# slo.net
KiCad netlist of a schematic drawn in EAGLE
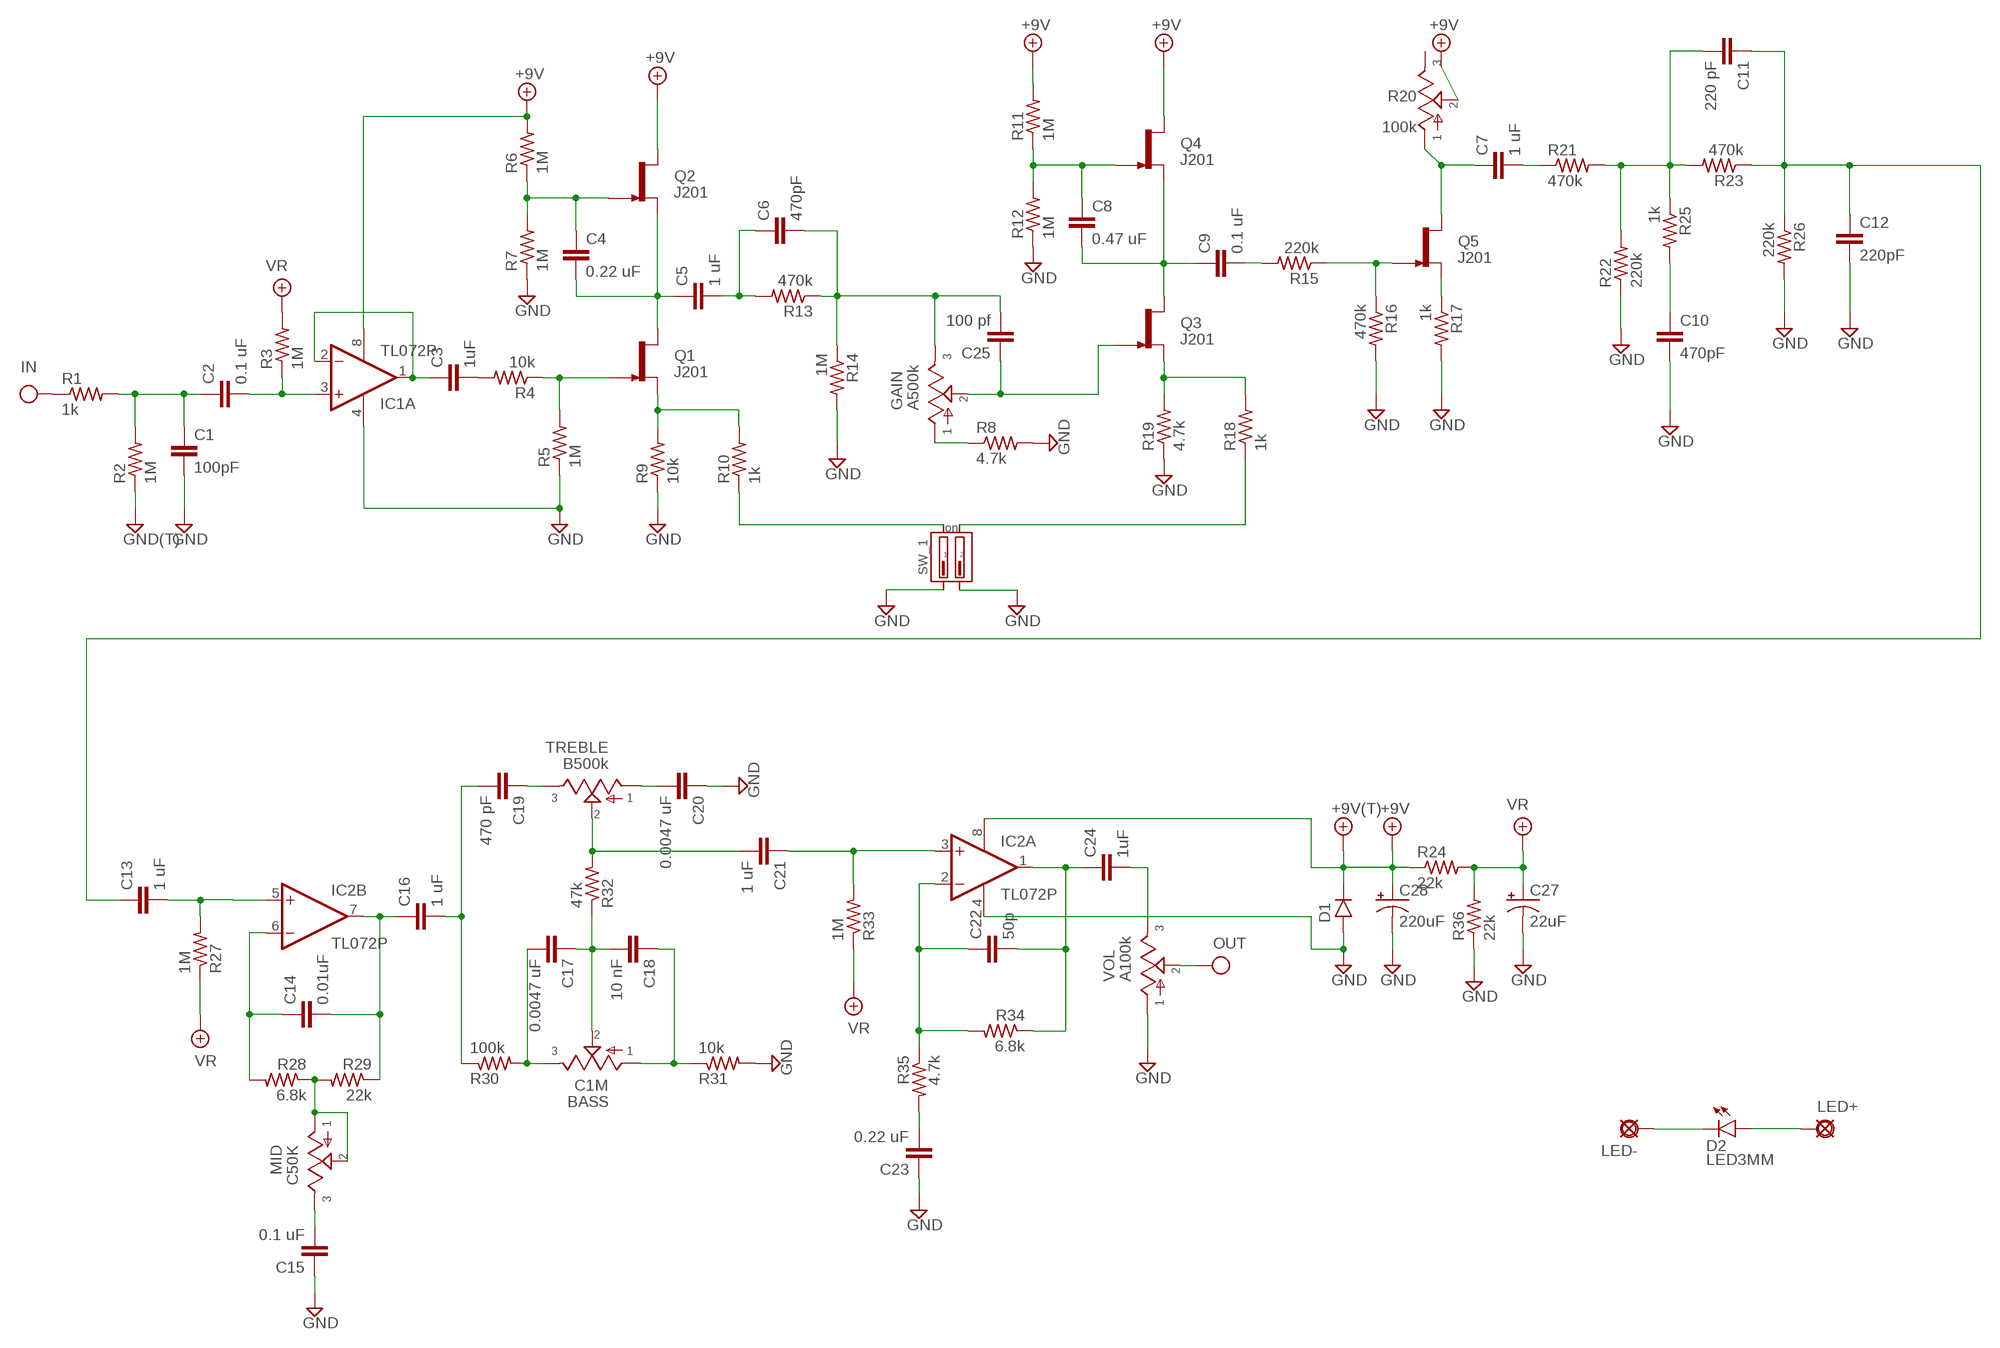
[diagram p0: schematic, sheet 1]

(export (version "E")
  (design (tool "Eeschema 10.0.6"))
  (components
    (comp (ref "+9V")
      (value "+9V(T)")
      (footprint "eagle-import:SQUARE")
      (libsource (lib "eagle-import") (part "+9V(T)"))
    )
    (comp (ref "BASS")
      (value "C1M")
      (footprint "eagle-import:16MM")
      (libsource (lib "eagle-import") (part "POT16MM"))
    )
    (comp (ref "C1")
      (value "100pF")
      (footprint "eagle-import:050X030_050")
      (libsource (lib "eagle-import") (part "050X030_0502"))
    )
    (comp (ref "C2")
      (value "0.1 uF")
      (footprint "eagle-import:080X045")
      (libsource (lib "eagle-import") (part "080X0452"))
    )
    (comp (ref "C3")
      (value "1uF")
      (footprint "eagle-import:080X050")
      (libsource (lib "eagle-import") (part "080X0502"))
    )
    (comp (ref "C4")
      (value "0.22 uF")
      (footprint "eagle-import:080X045")
      (libsource (lib "eagle-import") (part "080X0452"))
    )
    (comp (ref "C5")
      (value "1 uF")
      (footprint "eagle-import:070X030")
      (libsource (lib "eagle-import") (part "070X0302"))
    )
    (comp (ref "C6")
      (value "470pF")
      (footprint "eagle-import:050X030_050")
      (libsource (lib "eagle-import") (part "050X030_0502"))
    )
    (comp (ref "C7")
      (value "1 uF")
      (footprint "eagle-import:080X050")
      (libsource (lib "eagle-import") (part "080X0502"))
    )
    (comp (ref "C8")
      (value "0.47 uF")
      (footprint "eagle-import:080X045")
      (libsource (lib "eagle-import") (part "080X0452"))
    )
    (comp (ref "C9")
      (value "0.1 uF")
      (footprint "eagle-import:080X045")
      (libsource (lib "eagle-import") (part "080X0452"))
    )
    (comp (ref "C10")
      (value "470pF")
      (footprint "eagle-import:070X030")
      (libsource (lib "eagle-import") (part "070X0302"))
    )
    (comp (ref "C11")
      (value "220 pF")
      (footprint "eagle-import:075X035_3")
      (libsource (lib "eagle-import") (part "075X0353"))
    )
    (comp (ref "C12")
      (value "220pF")
      (footprint "eagle-import:075X035_3")
      (libsource (lib "eagle-import") (part "075X0353"))
    )
    (comp (ref "C13")
      (value "1 uF")
      (footprint "eagle-import:080X050")
      (libsource (lib "eagle-import") (part "080X0502"))
    )
    (comp (ref "C14")
      (value "0.01uF")
      (footprint "eagle-import:050X030_050_1")
      (libsource (lib "eagle-import") (part "050X030_0501"))
    )
    (comp (ref "C15")
      (value "0.1 uF")
      (footprint "eagle-import:075X040_3")
      (libsource (lib "eagle-import") (part "080X0453"))
    )
    (comp (ref "C16")
      (value "1 uF")
      (footprint "eagle-import:080X050")
      (libsource (lib "eagle-import") (part "080X0502"))
    )
    (comp (ref "C17")
      (value "0.0047 uF")
      (footprint "eagle-import:075X035")
      (libsource (lib "eagle-import") (part "075X0352"))
    )
    (comp (ref "C18")
      (value "10 nF")
      (footprint "eagle-import:075X035")
      (libsource (lib "eagle-import") (part "075X0352"))
    )
    (comp (ref "C19")
      (value "470 pF")
      (footprint "eagle-import:075X030")
      (libsource (lib "eagle-import") (part "075X0302"))
    )
    (comp (ref "C20")
      (value "0.0047 uF")
      (footprint "eagle-import:075X035")
      (libsource (lib "eagle-import") (part "075X0352"))
    )
    (comp (ref "C21")
      (value "1 uF")
      (footprint "eagle-import:080X050")
      (libsource (lib "eagle-import") (part "080X0502"))
    )
    (comp (ref "C22")
      (value "50p")
      (footprint "eagle-import:050X030_050_1")
      (libsource (lib "eagle-import") (part "050X030_0501"))
    )
    (comp (ref "C23")
      (value "0.22 uF")
      (footprint "eagle-import:080X045")
      (libsource (lib "eagle-import") (part "080X0452"))
    )
    (comp (ref "C24")
      (value "1uF")
      (footprint "eagle-import:080X050")
      (libsource (lib "eagle-import") (part "080X0502"))
    )
    (comp (ref "C25")
      (value "100 pf")
      (footprint "eagle-import:050X030_050_1")
      (libsource (lib "eagle-import") (part "050X030_0501"))
    )
    (comp (ref "C27")
      (value "22uF")
      (footprint "eagle-import:050_020")
      (libsource (lib "eagle-import") (part "050"))
    )
    (comp (ref "C28")
      (value "220uF")
      (footprint "eagle-import:063_025")
      (libsource (lib "eagle-import") (part "0631"))
    )
    (comp (ref "D1")
      (value "1N400X.1")
      (footprint "eagle-import:DO41-1")
      (libsource (lib "eagle-import") (part "1N400X.1"))
    )
    (comp (ref "D2")
      (value "LED3MM")
      (footprint "eagle-import:LED3MM")
      (libsource (lib "eagle-import") (part "LED3MM"))
    )
    (comp (ref "GAIN")
      (value "A500k")
      (footprint "eagle-import:16MM")
      (libsource (lib "eagle-import") (part "POT16MM"))
    )
    (comp (ref "GND")
      (value "GND(T)")
      (footprint "eagle-import:SQUARE")
      (libsource (lib "eagle-import") (part "GND(T)"))
    )
    (comp (ref "IC1")
      (value "TL072P")
      (footprint "eagle-import:DIL08")
      (libsource (lib "eagle-import") (part "TL072P"))
    )
    (comp (ref "IC2")
      (value "TL072P")
      (footprint "eagle-import:DIL08")
      (libsource (lib "eagle-import") (part "TL072P"))
    )
    (comp (ref "IN")
      (value "IN(T)")
      (footprint "eagle-import:SQUARE")
      (fields (field (name "SPICEPREFIX") "I"))
      (libsource (lib "eagle-import") (part "IN(T)"))
    )
    (comp (ref "LED+")
      (value "PADO")
      (footprint "eagle-import:ROUND")
      (libsource (lib "eagle-import") (part "PADO"))
    )
    (comp (ref "LED-")
      (value "PAD")
      (footprint "eagle-import:SQUARE")
      (libsource (lib "eagle-import") (part "PAD"))
    )
    (comp (ref "MID")
      (value "C50K")
      (footprint "eagle-import:16MM")
      (libsource (lib "eagle-import") (part "POT16MM"))
    )
    (comp (ref "OUT")
      (value "OUT(T)")
      (footprint "eagle-import:SQUARE")
      (libsource (lib "eagle-import") (part "OUT(T)"))
    )
    (comp (ref "Q1")
      (value "J201")
      (footprint "eagle-import:TO92-")
      (libsource (lib "eagle-import") (part "J201"))
    )
    (comp (ref "Q2")
      (value "J201")
      (footprint "eagle-import:TO92-")
      (libsource (lib "eagle-import") (part "J201"))
    )
    (comp (ref "Q3")
      (value "J201")
      (footprint "eagle-import:TO92-")
      (libsource (lib "eagle-import") (part "J201"))
    )
    (comp (ref "Q4")
      (value "J201")
      (footprint "eagle-import:TO92-")
      (libsource (lib "eagle-import") (part "J201"))
    )
    (comp (ref "Q5")
      (value "J201")
      (footprint "eagle-import:TO92-")
      (libsource (lib "eagle-import") (part "J201"))
    )
    (comp (ref "R1")
      (value "1k")
      (footprint "eagle-import:R0204_2")
      (libsource (lib "eagle-import") (part "3MM.2"))
    )
    (comp (ref "R2")
      (value "1M")
      (footprint "eagle-import:R0204_2")
      (libsource (lib "eagle-import") (part "3MM.2"))
    )
    (comp (ref "R3")
      (value "1M")
      (footprint "eagle-import:R0204_2")
      (libsource (lib "eagle-import") (part "3MM.2"))
    )
    (comp (ref "R4")
      (value "10k")
      (footprint "eagle-import:R0204_2")
      (libsource (lib "eagle-import") (part "3MM.2"))
    )
    (comp (ref "R5")
      (value "1M")
      (footprint "eagle-import:R0204_2")
      (libsource (lib "eagle-import") (part "3MM.2"))
    )
    (comp (ref "R6")
      (value "1M")
      (footprint "eagle-import:R0204_2")
      (libsource (lib "eagle-import") (part "3MM.2"))
    )
    (comp (ref "R7")
      (value "1M")
      (footprint "eagle-import:R0204_2")
      (libsource (lib "eagle-import") (part "3MM.2"))
    )
    (comp (ref "R8")
      (value "4.7k")
      (footprint "eagle-import:R0204_2")
      (libsource (lib "eagle-import") (part "3MM.2"))
    )
    (comp (ref "R9")
      (value "10k")
      (footprint "eagle-import:R0204_2")
      (libsource (lib "eagle-import") (part "3MM.2"))
    )
    (comp (ref "R10")
      (value "1k")
      (footprint "eagle-import:R0204_2")
      (libsource (lib "eagle-import") (part "3MM.2"))
    )
    (comp (ref "R11")
      (value "1M")
      (footprint "eagle-import:R0204_2")
      (libsource (lib "eagle-import") (part "3MM.2"))
    )
    (comp (ref "R12")
      (value "1M")
      (footprint "eagle-import:R0204_2")
      (libsource (lib "eagle-import") (part "3MM.2"))
    )
    (comp (ref "R13")
      (value "470k")
      (footprint "eagle-import:R0204_2")
      (libsource (lib "eagle-import") (part "3MM.2"))
    )
    (comp (ref "R14")
      (value "1M")
      (footprint "eagle-import:R0204_2")
      (libsource (lib "eagle-import") (part "3MM.2"))
    )
    (comp (ref "R15")
      (value "220k")
      (footprint "eagle-import:R0204_2")
      (libsource (lib "eagle-import") (part "3MM.2"))
    )
    (comp (ref "R16")
      (value "470k")
      (footprint "eagle-import:R0204_2")
      (libsource (lib "eagle-import") (part "3MM.2"))
    )
    (comp (ref "R17")
      (value "1k")
      (footprint "eagle-import:R0204_2")
      (libsource (lib "eagle-import") (part "3MM.2"))
    )
    (comp (ref "R18")
      (value "1k")
      (footprint "eagle-import:R0204_2")
      (libsource (lib "eagle-import") (part "3MM.2"))
    )
    (comp (ref "R19")
      (value "4.7k")
      (footprint "eagle-import:R0204_2")
      (libsource (lib "eagle-import") (part "3MM.2"))
    )
    (comp (ref "R20")
      (value "100k")
      (footprint "eagle-import:B25P")
      (libsource (lib "eagle-import") (part "POTTRIM"))
    )
    (comp (ref "R21")
      (value "470k")
      (footprint "eagle-import:R0204_2")
      (libsource (lib "eagle-import") (part "3MM.2"))
    )
    (comp (ref "R22")
      (value "220k")
      (footprint "eagle-import:R0204_2")
      (libsource (lib "eagle-import") (part "3MM.2"))
    )
    (comp (ref "R23")
      (value "470k")
      (footprint "eagle-import:R0204_2")
      (libsource (lib "eagle-import") (part "3MM.2"))
    )
    (comp (ref "R24")
      (value "22k")
      (footprint "eagle-import:R0204_2")
      (libsource (lib "eagle-import") (part "3MM.2"))
    )
    (comp (ref "R25")
      (value "1k")
      (footprint "eagle-import:R0204_2")
      (libsource (lib "eagle-import") (part "3MM.2"))
    )
    (comp (ref "R26")
      (value "220k")
      (footprint "eagle-import:R0204_2")
      (libsource (lib "eagle-import") (part "3MM.2"))
    )
    (comp (ref "R27")
      (value "1M")
      (footprint "eagle-import:R0204_2")
      (libsource (lib "eagle-import") (part "3MM.2"))
    )
    (comp (ref "R28")
      (value "6.8k")
      (footprint "eagle-import:R0204_2")
      (libsource (lib "eagle-import") (part "3MM.2"))
    )
    (comp (ref "R29")
      (value "22k")
      (footprint "eagle-import:R0204_2")
      (libsource (lib "eagle-import") (part "3MM.2"))
    )
    (comp (ref "R30")
      (value "100k")
      (footprint "eagle-import:R0204_2")
      (libsource (lib "eagle-import") (part "3MM.2"))
    )
    (comp (ref "R31")
      (value "10k")
      (footprint "eagle-import:R0204_2")
      (libsource (lib "eagle-import") (part "3MM.2"))
    )
    (comp (ref "R32")
      (value "47k")
      (footprint "eagle-import:R0204_2")
      (libsource (lib "eagle-import") (part "3MM.2"))
    )
    (comp (ref "R33")
      (value "1M")
      (footprint "eagle-import:R0204_2")
      (libsource (lib "eagle-import") (part "3MM.2"))
    )
    (comp (ref "R34")
      (value "6.8k")
      (footprint "eagle-import:R0204_2")
      (libsource (lib "eagle-import") (part "3MM.2"))
    )
    (comp (ref "R35")
      (value "4.7k")
      (footprint "eagle-import:R0204_2")
      (libsource (lib "eagle-import") (part "3MM.2"))
    )
    (comp (ref "R36")
      (value "22k")
      (footprint "eagle-import:R0204_2")
      (libsource (lib "eagle-import") (part "3MM.2"))
    )
    (comp (ref "SW_1")
      (value "DIP2")
      (footprint "eagle-import:DIP2.B")
      (libsource (lib "eagle-import") (part "DIP2"))
    )
    (comp (ref "TREBLE")
      (value "B500k")
      (footprint "eagle-import:16MM")
      (libsource (lib "eagle-import") (part "POT16MM"))
    )
    (comp (ref "VOL")
      (value "A100k")
      (footprint "eagle-import:16MM")
      (libsource (lib "eagle-import") (part "POT16MM"))
    )
  )
  (nets
    (net (code "1") (name "+9V") (class "Default")
      (node (ref "+9V") (pin "1") (pinfunction "+9V_1") (pintype "power_in"))
      (node (ref "C28") (pin "+") (pinfunction "+_+") (pintype "passive"))
      (node (ref "D1") (pin "C") (pinfunction "C_C") (pintype "passive"))
      (node (ref "IC1") (pin "8") (pinfunction "V+_8") (pintype "power_in"))
      (node (ref "IC2") (pin "8") (pinfunction "V+_8") (pintype "power_in"))
      (node (ref "Q2") (pin "3") (pinfunction "D_3") (pintype "passive"))
      (node (ref "Q4") (pin "3") (pinfunction "D_3") (pintype "passive"))
      (node (ref "R11") (pin "2") (pinfunction "2_2") (pintype "passive"))
      (node (ref "R20") (pin "2") (pinfunction "2_2") (pintype "passive"))
      (node (ref "R24") (pin "1") (pinfunction "1_1") (pintype "passive"))
      (node (ref "R6") (pin "2") (pinfunction "2_2") (pintype "passive"))
    )
    (net (code "2") (name "GND") (class "Default")
      (node (ref "C1") (pin "2") (pinfunction "2_2") (pintype "passive"))
      (node (ref "C10") (pin "2") (pinfunction "2_2") (pintype "passive"))
      (node (ref "C12") (pin "2") (pinfunction "2_2") (pintype "passive"))
      (node (ref "C15") (pin "1") (pinfunction "1_1") (pintype "passive"))
      (node (ref "C20") (pin "1") (pinfunction "1_1") (pintype "passive"))
      (node (ref "C23") (pin "1") (pinfunction "1_1") (pintype "passive"))
      (node (ref "C27") (pin "-") (pinfunction "-_-") (pintype "passive"))
      (node (ref "C28") (pin "-") (pinfunction "-_-") (pintype "passive"))
      (node (ref "D1") (pin "A") (pinfunction "A_A") (pintype "passive"))
      (node (ref "GND") (pin "1") (pinfunction "GND_1") (pintype "power_in"))
      (node (ref "IC1") (pin "4") (pinfunction "V-_4") (pintype "power_in"))
      (node (ref "IC2") (pin "4") (pinfunction "V-_4") (pintype "power_in"))
      (node (ref "R12") (pin "1") (pinfunction "1_1") (pintype "passive"))
      (node (ref "R14") (pin "2") (pinfunction "2_2") (pintype "passive"))
      (node (ref "R16") (pin "2") (pinfunction "2_2") (pintype "passive"))
      (node (ref "R17") (pin "2") (pinfunction "2_2") (pintype "passive"))
      (node (ref "R19") (pin "1") (pinfunction "1_1") (pintype "passive"))
      (node (ref "R2") (pin "1") (pinfunction "1_1") (pintype "passive"))
      (node (ref "R22") (pin "1") (pinfunction "1_1") (pintype "passive"))
      (node (ref "R26") (pin "2") (pinfunction "2_2") (pintype "passive"))
      (node (ref "R31") (pin "2") (pinfunction "2_2") (pintype "passive"))
      (node (ref "R36") (pin "1") (pinfunction "1_1") (pintype "passive"))
      (node (ref "R5") (pin "1") (pinfunction "1_1") (pintype "passive"))
      (node (ref "R7") (pin "1") (pinfunction "1_1") (pintype "passive"))
      (node (ref "R8") (pin "2") (pinfunction "2_2") (pintype "passive"))
      (node (ref "R9") (pin "1") (pinfunction "1_1") (pintype "passive"))
      (node (ref "SW_1") (pin "P$1") (pinfunction "1_P$1") (pintype "bidirectional"))
      (node (ref "SW_1") (pin "P$3") (pinfunction "3_P$3") (pintype "bidirectional"))
      (node (ref "VOL") (pin "1") (pinfunction "1_1") (pintype "passive"))
    )
    (net (code "3") (name "IN(T)") (class "Default")
      (node (ref "IN") (pin "1") (pinfunction "IN_1") (pintype "power_in"))
      (node (ref "R1") (pin "1") (pinfunction "1_1") (pintype "passive"))
    )
    (net (code "4") (name "Net-(BASS-Pad1)") (class "Default")
      (node (ref "BASS") (pin "1") (pinfunction "1_1") (pintype "passive"))
      (node (ref "C18") (pin "1") (pinfunction "1_1") (pintype "passive"))
      (node (ref "R31") (pin "1") (pinfunction "1_1") (pintype "passive"))
    )
    (net (code "5") (name "Net-(BASS-Pad2)") (class "Default")
      (node (ref "BASS") (pin "2") (pinfunction "2_2") (pintype "passive"))
      (node (ref "C17") (pin "1") (pinfunction "1_1") (pintype "passive"))
      (node (ref "C18") (pin "2") (pinfunction "2_2") (pintype "passive"))
      (node (ref "R32") (pin "1") (pinfunction "1_1") (pintype "passive"))
    )
    (net (code "6") (name "Net-(BASS-Pad3)") (class "Default")
      (node (ref "BASS") (pin "3") (pinfunction "3_3") (pintype "passive"))
      (node (ref "C17") (pin "2") (pinfunction "2_2") (pintype "passive"))
      (node (ref "R30") (pin "2") (pinfunction "2_2") (pintype "passive"))
    )
    (net (code "7") (name "Net-(C1-Pad1)") (class "Default")
      (node (ref "C1") (pin "1") (pinfunction "1_1") (pintype "passive"))
      (node (ref "C2") (pin "1") (pinfunction "1_1") (pintype "passive"))
      (node (ref "R1") (pin "2") (pinfunction "2_2") (pintype "passive"))
      (node (ref "R2") (pin "2") (pinfunction "2_2") (pintype "passive"))
    )
    (net (code "8") (name "Net-(C3-Pad2)") (class "Default")
      (node (ref "C3") (pin "2") (pinfunction "2_2") (pintype "passive"))
      (node (ref "R4") (pin "2") (pinfunction "2_2") (pintype "passive"))
    )
    (net (code "9") (name "Net-(C5-Pad2)") (class "Default")
      (node (ref "C5") (pin "2") (pinfunction "2_2") (pintype "passive"))
      (node (ref "C6") (pin "1") (pinfunction "1_1") (pintype "passive"))
      (node (ref "R13") (pin "2") (pinfunction "2_2") (pintype "passive"))
    )
    (net (code "10") (name "Net-(C7-Pad2)") (class "Default")
      (node (ref "C7") (pin "2") (pinfunction "2_2") (pintype "passive"))
      (node (ref "R21") (pin "1") (pinfunction "1_1") (pintype "passive"))
    )
    (net (code "11") (name "Net-(C9-Pad2)") (class "Default")
      (node (ref "C9") (pin "2") (pinfunction "2_2") (pintype "passive"))
      (node (ref "R15") (pin "2") (pinfunction "2_2") (pintype "passive"))
    )
    (net (code "12") (name "Net-(C10-Pad1)") (class "Default")
      (node (ref "C10") (pin "1") (pinfunction "1_1") (pintype "passive"))
      (node (ref "R25") (pin "2") (pinfunction "2_2") (pintype "passive"))
    )
    (net (code "13") (name "Net-(C11-Pad1)") (class "Default")
      (node (ref "C11") (pin "1") (pinfunction "1_1") (pintype "passive"))
      (node (ref "C12") (pin "1") (pinfunction "1_1") (pintype "passive"))
      (node (ref "C13") (pin "1") (pinfunction "1_1") (pintype "passive"))
      (node (ref "R23") (pin "1") (pinfunction "1_1") (pintype "passive"))
      (node (ref "R26") (pin "1") (pinfunction "1_1") (pintype "passive"))
    )
    (net (code "14") (name "Net-(C11-Pad2)") (class "Default")
      (node (ref "C11") (pin "2") (pinfunction "2_2") (pintype "passive"))
      (node (ref "R21") (pin "2") (pinfunction "2_2") (pintype "passive"))
      (node (ref "R22") (pin "2") (pinfunction "2_2") (pintype "passive"))
      (node (ref "R23") (pin "2") (pinfunction "2_2") (pintype "passive"))
      (node (ref "R25") (pin "1") (pinfunction "1_1") (pintype "passive"))
    )
    (net (code "15") (name "Net-(C15-Pad2)") (class "Default")
      (node (ref "C15") (pin "2") (pinfunction "2_2") (pintype "passive"))
      (node (ref "MID") (pin "3") (pinfunction "3_3") (pintype "passive"))
    )
    (net (code "16") (name "Net-(C16-Pad2)") (class "Default")
      (node (ref "C16") (pin "2") (pinfunction "2_2") (pintype "passive"))
      (node (ref "C19") (pin "2") (pinfunction "2_2") (pintype "passive"))
      (node (ref "R30") (pin "1") (pinfunction "1_1") (pintype "passive"))
    )
    (net (code "17") (name "Net-(C19-Pad1)") (class "Default")
      (node (ref "C19") (pin "1") (pinfunction "1_1") (pintype "passive"))
      (node (ref "TREBLE") (pin "3") (pinfunction "3_3") (pintype "passive"))
    )
    (net (code "18") (name "Net-(C20-Pad2)") (class "Default")
      (node (ref "C20") (pin "2") (pinfunction "2_2") (pintype "passive"))
      (node (ref "TREBLE") (pin "1") (pinfunction "1_1") (pintype "passive"))
    )
    (net (code "19") (name "Net-(C21-Pad2)") (class "Default")
      (node (ref "C21") (pin "2") (pinfunction "2_2") (pintype "passive"))
      (node (ref "R32") (pin "2") (pinfunction "2_2") (pintype "passive"))
      (node (ref "TREBLE") (pin "2") (pinfunction "2_2") (pintype "passive"))
    )
    (net (code "20") (name "Net-(C23-Pad2)") (class "Default")
      (node (ref "C23") (pin "2") (pinfunction "2_2") (pintype "passive"))
      (node (ref "R35") (pin "2") (pinfunction "2_2") (pintype "passive"))
    )
    (net (code "21") (name "Net-(C24-Pad2)") (class "Default")
      (node (ref "C24") (pin "2") (pinfunction "2_2") (pintype "passive"))
      (node (ref "VOL") (pin "3") (pinfunction "3_3") (pintype "passive"))
    )
    (net (code "22") (name "Net-(C25-Pad2)") (class "Default")
      (node (ref "C25") (pin "2") (pinfunction "2_2") (pintype "passive"))
      (node (ref "C6") (pin "2") (pinfunction "2_2") (pintype "passive"))
      (node (ref "GAIN") (pin "3") (pinfunction "3_3") (pintype "passive"))
      (node (ref "R13") (pin "1") (pinfunction "1_1") (pintype "passive"))
      (node (ref "R14") (pin "1") (pinfunction "1_1") (pintype "passive"))
    )
    (net (code "23") (name "Net-(D2-C)") (class "Default")
      (node (ref "D2") (pin "K") (pinfunction "C_K") (pintype "passive"))
      (node (ref "LED-") (pin "1") (pinfunction "PAD_1") (pintype "passive"))
    )
    (net (code "24") (name "Net-(GAIN-Pad1)") (class "Default")
      (node (ref "GAIN") (pin "1") (pinfunction "1_1") (pintype "passive"))
      (node (ref "R8") (pin "1") (pinfunction "1_1") (pintype "passive"))
    )
    (net (code "25") (name "Net-(IC1A-+IN)") (class "Default")
      (node (ref "C2") (pin "2") (pinfunction "2_2") (pintype "passive"))
      (node (ref "IC1") (pin "3") (pinfunction "+IN_3") (pintype "input"))
      (node (ref "R3") (pin "1") (pinfunction "1_1") (pintype "passive"))
    )
    (net (code "26") (name "Net-(IC1A--IN)") (class "Default")
      (node (ref "C3") (pin "1") (pinfunction "1_1") (pintype "passive"))
      (node (ref "IC1") (pin "1") (pinfunction "OUT_1") (pintype "output"))
      (node (ref "IC1") (pin "2") (pinfunction "-IN_2") (pintype "input"))
    )
    (net (code "27") (name "Net-(IC2A-+IN)") (class "Default")
      (node (ref "C21") (pin "1") (pinfunction "1_1") (pintype "passive"))
      (node (ref "IC2") (pin "3") (pinfunction "+IN_3") (pintype "input"))
      (node (ref "R33") (pin "2") (pinfunction "2_2") (pintype "passive"))
    )
    (net (code "28") (name "Net-(IC2A--IN)") (class "Default")
      (node (ref "C22") (pin "1") (pinfunction "1_1") (pintype "passive"))
      (node (ref "IC2") (pin "2") (pinfunction "-IN_2") (pintype "input"))
      (node (ref "R34") (pin "2") (pinfunction "2_2") (pintype "passive"))
      (node (ref "R35") (pin "1") (pinfunction "1_1") (pintype "passive"))
    )
    (net (code "29") (name "Net-(IC2A-OUT)") (class "Default")
      (node (ref "C22") (pin "2") (pinfunction "2_2") (pintype "passive"))
      (node (ref "C24") (pin "1") (pinfunction "1_1") (pintype "passive"))
      (node (ref "IC2") (pin "1") (pinfunction "OUT_1") (pintype "output"))
      (node (ref "R34") (pin "1") (pinfunction "1_1") (pintype "passive"))
    )
    (net (code "30") (name "Net-(IC2B-+IN)") (class "Default")
      (node (ref "C13") (pin "2") (pinfunction "2_2") (pintype "passive"))
      (node (ref "IC2") (pin "5") (pinfunction "+IN_5") (pintype "input"))
      (node (ref "R27") (pin "2") (pinfunction "2_2") (pintype "passive"))
    )
    (net (code "31") (name "Net-(IC2B--IN)") (class "Default")
      (node (ref "C14") (pin "1") (pinfunction "1_1") (pintype "passive"))
      (node (ref "IC2") (pin "6") (pinfunction "-IN_6") (pintype "input"))
      (node (ref "R28") (pin "2") (pinfunction "2_2") (pintype "passive"))
    )
    (net (code "32") (name "Net-(IC2B-OUT)") (class "Default")
      (node (ref "C14") (pin "2") (pinfunction "2_2") (pintype "passive"))
      (node (ref "C16") (pin "1") (pinfunction "1_1") (pintype "passive"))
      (node (ref "IC2") (pin "7") (pinfunction "OUT_7") (pintype "output"))
      (node (ref "R29") (pin "1") (pinfunction "1_1") (pintype "passive"))
    )
    (net (code "33") (name "Net-(LED+-PAD)") (class "Default")
      (node (ref "D2") (pin "A") (pinfunction "A_A") (pintype "passive"))
      (node (ref "LED+") (pin "1") (pinfunction "PAD_1") (pintype "passive"))
    )
    (net (code "34") (name "Net-(MID-Pad1)") (class "Default")
      (node (ref "MID") (pin "1") (pinfunction "1_1") (pintype "passive"))
      (node (ref "MID") (pin "2") (pinfunction "2_2") (pintype "passive"))
      (node (ref "R28") (pin "1") (pinfunction "1_1") (pintype "passive"))
      (node (ref "R29") (pin "2") (pinfunction "2_2") (pintype "passive"))
    )
    (net (code "35") (name "Net-(Q1-D)") (class "Default")
      (node (ref "C4") (pin "2") (pinfunction "2_2") (pintype "passive"))
      (node (ref "C5") (pin "1") (pinfunction "1_1") (pintype "passive"))
      (node (ref "Q1") (pin "3") (pinfunction "D_3") (pintype "passive"))
      (node (ref "Q2") (pin "2") (pinfunction "S_2") (pintype "passive"))
    )
    (net (code "36") (name "Net-(Q1-G)") (class "Default")
      (node (ref "Q1") (pin "1") (pinfunction "G_1") (pintype "passive"))
      (node (ref "R4") (pin "1") (pinfunction "1_1") (pintype "passive"))
      (node (ref "R5") (pin "2") (pinfunction "2_2") (pintype "passive"))
    )
    (net (code "37") (name "Net-(Q1-S)") (class "Default")
      (node (ref "Q1") (pin "2") (pinfunction "S_2") (pintype "passive"))
      (node (ref "R10") (pin "2") (pinfunction "2_2") (pintype "passive"))
      (node (ref "R9") (pin "2") (pinfunction "2_2") (pintype "passive"))
    )
    (net (code "38") (name "Net-(Q2-G)") (class "Default")
      (node (ref "C4") (pin "1") (pinfunction "1_1") (pintype "passive"))
      (node (ref "Q2") (pin "1") (pinfunction "G_1") (pintype "passive"))
      (node (ref "R6") (pin "1") (pinfunction "1_1") (pintype "passive"))
      (node (ref "R7") (pin "2") (pinfunction "2_2") (pintype "passive"))
    )
    (net (code "39") (name "Net-(Q3-D)") (class "Default")
      (node (ref "C8") (pin "2") (pinfunction "2_2") (pintype "passive"))
      (node (ref "C9") (pin "1") (pinfunction "1_1") (pintype "passive"))
      (node (ref "Q3") (pin "3") (pinfunction "D_3") (pintype "passive"))
      (node (ref "Q4") (pin "2") (pinfunction "S_2") (pintype "passive"))
    )
    (net (code "40") (name "Net-(Q3-G)") (class "Default")
      (node (ref "C25") (pin "1") (pinfunction "1_1") (pintype "passive"))
      (node (ref "GAIN") (pin "2") (pinfunction "2_2") (pintype "passive"))
      (node (ref "Q3") (pin "1") (pinfunction "G_1") (pintype "passive"))
    )
    (net (code "41") (name "Net-(Q3-S)") (class "Default")
      (node (ref "Q3") (pin "2") (pinfunction "S_2") (pintype "passive"))
      (node (ref "R18") (pin "2") (pinfunction "2_2") (pintype "passive"))
      (node (ref "R19") (pin "2") (pinfunction "2_2") (pintype "passive"))
    )
    (net (code "42") (name "Net-(Q4-G)") (class "Default")
      (node (ref "C8") (pin "1") (pinfunction "1_1") (pintype "passive"))
      (node (ref "Q4") (pin "1") (pinfunction "G_1") (pintype "passive"))
      (node (ref "R11") (pin "1") (pinfunction "1_1") (pintype "passive"))
      (node (ref "R12") (pin "2") (pinfunction "2_2") (pintype "passive"))
    )
    (net (code "43") (name "Net-(Q5-D)") (class "Default")
      (node (ref "C7") (pin "1") (pinfunction "1_1") (pintype "passive"))
      (node (ref "Q5") (pin "3") (pinfunction "D_3") (pintype "passive"))
      (node (ref "R20") (pin "1") (pinfunction "1_1") (pintype "passive"))
    )
    (net (code "44") (name "Net-(Q5-G)") (class "Default")
      (node (ref "Q5") (pin "1") (pinfunction "G_1") (pintype "passive"))
      (node (ref "R15") (pin "1") (pinfunction "1_1") (pintype "passive"))
      (node (ref "R16") (pin "1") (pinfunction "1_1") (pintype "passive"))
    )
    (net (code "45") (name "Net-(Q5-S)") (class "Default")
      (node (ref "Q5") (pin "2") (pinfunction "S_2") (pintype "passive"))
      (node (ref "R17") (pin "1") (pinfunction "1_1") (pintype "passive"))
    )
    (net (code "46") (name "Net-(SW_1-2)") (class "Default")
      (node (ref "R10") (pin "1") (pinfunction "1_1") (pintype "passive"))
      (node (ref "SW_1") (pin "P$2") (pinfunction "2_P$2") (pintype "bidirectional"))
    )
    (net (code "47") (name "Net-(SW_1-4)") (class "Default")
      (node (ref "R18") (pin "1") (pinfunction "1_1") (pintype "passive"))
      (node (ref "SW_1") (pin "P$4") (pinfunction "4_P$4") (pintype "bidirectional"))
    )
    (net (code "48") (name "OUT(T)") (class "Default")
      (node (ref "OUT") (pin "1") (pinfunction "OUT_1") (pintype "power_in"))
      (node (ref "VOL") (pin "2") (pinfunction "2_2") (pintype "passive"))
    )
    (net (code "49") (name "VR") (class "Default")
      (node (ref "C27") (pin "+") (pinfunction "+_+") (pintype "passive"))
      (node (ref "R24") (pin "2") (pinfunction "2_2") (pintype "passive"))
      (node (ref "R27") (pin "1") (pinfunction "1_1") (pintype "passive"))
      (node (ref "R3") (pin "2") (pinfunction "2_2") (pintype "passive"))
      (node (ref "R33") (pin "1") (pinfunction "1_1") (pintype "passive"))
      (node (ref "R36") (pin "2") (pinfunction "2_2") (pintype "passive"))
    )
    (net (code "50") (name "unconnected-(R20-Pad3)") (class "Default")
      (node (ref "R20") (pin "3") (pinfunction "3_3") (pintype "passive"))
    )
  )
)
